# SCH_Project-SappY_2026-01-27.net
KiCad netlist of a schematic drawn in EasyEDA
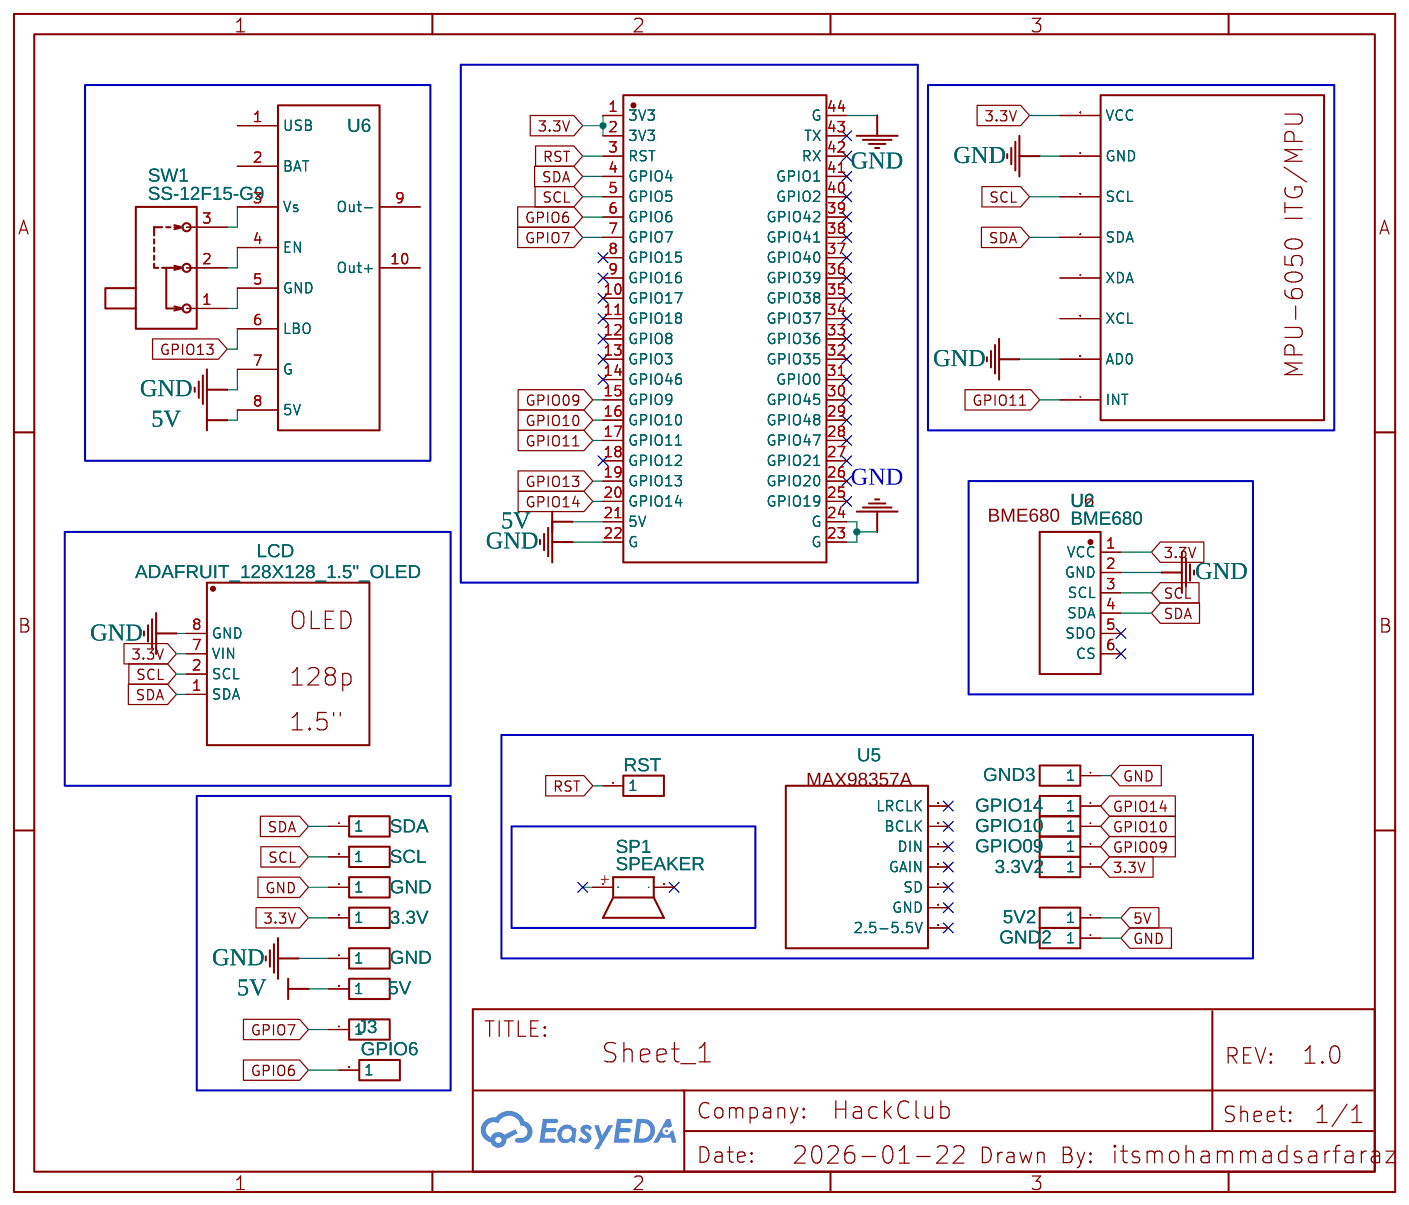
[diagram p0: schematic sheet]

(export (version "E")
  (design (tool "Eeschema 10.0.6"))
  (components
    (comp (ref "3.3V") (value "HDR-M-2.54_1x1") (libsource (lib "") (part "HDR-M-2.54_1x1_2")))
    (comp (ref "3.3V2") (value "HDR-M-2.54_1x1") (libsource (lib "") (part "HDR-M-2.54_1x1_8")))
    (comp (ref "5V2") (value "HDR-M-2.54_1x1") (libsource (lib "") (part "HDR-M-2.54_1x1_7")))
    (comp (ref "GND") (value "HDR-M-2.54_1x1") (libsource (lib "") (part "HDR-M-2.54_1x1_4")))
    (comp (ref "GND2") (value "HDR-M-2.54_1x1") (libsource (lib "") (part "HDR-M-2.54_1x1_5")))
    (comp (ref "GND3") (value "HDR-M-2.54_1x1") (libsource (lib "") (part "HDR-M-2.54_1x1_5")))
    (comp (ref "GPIO09") (value "HDR-M-2.54_1x1") (libsource (lib "") (part "HDR-M-2.54_1x1_1")))
    (comp (ref "GPIO10") (value "HDR-M-2.54_1x1") (libsource (lib "") (part "HDR-M-2.54_1x1_1")))
    (comp (ref "GPIO14") (value "HDR-M-2.54_1x1") (libsource (lib "") (part "HDR-M-2.54_1x1_1")))
    (comp (ref "J1") (value "GND") (libsource (lib "") (part "HDR-M-2.54_1x1")))
    (comp (ref "J2") (value "5V") (libsource (lib "") (part "HDR-M-2.54_1x1")))
    (comp (ref "J3") (value "HDR-M-2.54_1x1") (libsource (lib "") (part "HDR-M-2.54_1x1")))
    (comp (ref "J5") (value "GPIO6") (libsource (lib "") (part "HDR-M-2.54_1x1")))
    (comp (ref "LCD")
      (value "ADAFRUIT_128X128_1.5\"_OLED")
      (fields (field (name "Manufacturer Part") "MSP1503"))
      (libsource (lib "") (part "ADAFRUIT_128X128_1.5{dblquote}_OLED"))
    )
    (comp (ref "RST") (value "HDR-M-2.54_1x1") (libsource (lib "") (part "HDR-M-2.54_1x1_6")))
    (comp (ref "SCL") (value "HDR-M-2.54_1x1") (libsource (lib "") (part "HDR-M-2.54_1x1_9")))
    (comp (ref "SDA") (value "HDR-M-2.54_1x1") (libsource (lib "") (part "HDR-M-2.54_1x1_3")))
    (comp (ref "SP1") (value "SPEAKER") (libsource (lib "") (part "SPEAKER")))
    (comp (ref "SW1")
      (value "SS-12F15-G9")
      (fields (field (name "Manufacturer") "DEALON(德艺隆)"))
      (libsource (lib "") (part "SS-12F15-G9"))
    )
    (comp (ref "U1") (value "MPU-6050 ITG/MPU") (libsource (lib "") (part "MPU-6050 ITG/MPU")))
    (comp (ref "U2") (value "BME680") (libsource (lib "") (part "BME680")))
    (comp (ref "U4")
      (value "ESP32-S3-DevKitM-1U-N8")
      (fields
        (field (name "Manufacturer Part") "ESP32-S3-DevKitM-1")
        (field (name "Manufacturer") "Espressif")
      )
      (libsource (lib "") (part "ESP32-S3-DevKitM-1U-N8"))
    )
    (comp (ref "U5")
      (value "I2S MAX98357A MODULE")
      (fields (field (name "Manufacturer Part") "3006") (field (name "Manufacturer") "Adafruit"))
      (libsource (lib "") (part "I2S MAX98357A MODULE"))
    )
    (comp (ref "U6")
      (value "Adafruit Powerboost 1000C footprint")
      (fields (field (name "Manufacturer Part") "ada2465") (field (name "Manufacturer") "Adafruit"))
      (libsource (lib "") (part "Adafruit Powerboost 1000C footprint"))
    )
  )
  (nets
    (net (code "1") (name "3.3V") (class "Default")
      (node (ref "3.3V") (pin "1") (pinfunction "1_1") (pintype "input"))
      (node (ref "3.3V2") (pin "1") (pinfunction "1_1") (pintype "input"))
      (node (ref "LCD") (pin "7") (pinfunction "VIN_7") (pintype "unspecified"))
      (node (ref "U1") (pin "0") (pinfunction "VCC_0") (pintype "unspecified"))
      (node (ref "U2") (pin "1") (pinfunction "VCC_1") (pintype "unspecified"))
      (node (ref "U4") (pin "1") (pinfunction "3V3_1") (pintype "unspecified"))
      (node (ref "U4") (pin "2") (pinfunction "3V3_2") (pintype "unspecified"))
    )
    (net (code "2") (name "5V") (class "Default")
      (node (ref "5V2") (pin "1") (pinfunction "1_1") (pintype "input"))
      (node (ref "J2") (pin "1") (pinfunction "1_1") (pintype "input"))
      (node (ref "U4") (pin "21") (pinfunction "5V_21") (pintype "unspecified"))
      (node (ref "U6") (pin "8") (pinfunction "5V_8") (pintype "unspecified"))
    )
    (net (code "3") (name "GND") (class "Default")
      (node (ref "GND") (pin "1") (pinfunction "1_1") (pintype "input"))
      (node (ref "GND2") (pin "1") (pinfunction "1_1") (pintype "input"))
      (node (ref "GND3") (pin "1") (pinfunction "1_1") (pintype "input"))
      (node (ref "J1") (pin "1") (pinfunction "1_1") (pintype "input"))
      (node (ref "LCD") (pin "8") (pinfunction "GND_8") (pintype "unspecified"))
      (node (ref "U1") (pin "1") (pinfunction "GND_1") (pintype "unspecified"))
      (node (ref "U1") (pin "6") (pinfunction "AD0_6") (pintype "unspecified"))
      (node (ref "U2") (pin "2") (pinfunction "GND_2") (pintype "unspecified"))
      (node (ref "U4") (pin "22") (pinfunction "G_22") (pintype "unspecified"))
      (node (ref "U4") (pin "23") (pinfunction "G_23") (pintype "unspecified"))
      (node (ref "U4") (pin "24") (pinfunction "G_24") (pintype "unspecified"))
      (node (ref "U4") (pin "44") (pinfunction "G_44") (pintype "unspecified"))
      (node (ref "U6") (pin "7") (pinfunction "G_7") (pintype "unspecified"))
    )
    (net (code "4") (name "GPIO6") (class "Default")
      (node (ref "J3") (pin "1") (pinfunction "1_1") (pintype "input"))
      (node (ref "U4") (pin "6") (pinfunction "GPIO6_6") (pintype "unspecified"))
    )
    (net (code "5") (name "GPIO7") (class "Default")
      (node (ref "J5") (pin "1") (pinfunction "1_1") (pintype "input"))
      (node (ref "U4") (pin "7") (pinfunction "GPIO7_7") (pintype "unspecified"))
    )
    (net (code "6") (name "GPIO09") (class "Default")
      (node (ref "GPIO09") (pin "1") (pinfunction "1_1") (pintype "input"))
      (node (ref "U4") (pin "15") (pinfunction "GPIO9_15") (pintype "unspecified"))
    )
    (net (code "7") (name "GPIO10") (class "Default")
      (node (ref "GPIO10") (pin "1") (pinfunction "1_1") (pintype "input"))
      (node (ref "U4") (pin "16") (pinfunction "GPIO10_16") (pintype "unspecified"))
    )
    (net (code "8") (name "GPIO11") (class "Default")
      (node (ref "U1") (pin "7") (pinfunction "INT_7") (pintype "unspecified"))
      (node (ref "U4") (pin "17") (pinfunction "GPIO11_17") (pintype "unspecified"))
    )
    (net (code "9") (name "GPIO13") (class "Default")
      (node (ref "U4") (pin "19") (pinfunction "GPIO13_19") (pintype "unspecified"))
      (node (ref "U6") (pin "6") (pinfunction "LBO_6") (pintype "unspecified"))
    )
    (net (code "10") (name "GPIO14") (class "Default")
      (node (ref "GPIO14") (pin "1") (pinfunction "1_1") (pintype "input"))
      (node (ref "U4") (pin "20") (pinfunction "GPIO14_20") (pintype "unspecified"))
    )
    (net (code "11") (name "Net-(U6-EN)") (class "Default")
      (node (ref "SW1") (pin "2") (pinfunction "2_2") (pintype "unspecified"))
      (node (ref "U6") (pin "4") (pinfunction "EN_4") (pintype "unspecified"))
    )
    (net (code "12") (name "Net-(U6-GND)") (class "Default")
      (node (ref "SW1") (pin "1") (pinfunction "1_1") (pintype "unspecified"))
      (node (ref "U6") (pin "5") (pinfunction "GND_5") (pintype "unspecified"))
    )
    (net (code "13") (name "Net-(U6-Vs)") (class "Default")
      (node (ref "SW1") (pin "3") (pinfunction "3_3") (pintype "unspecified"))
      (node (ref "U6") (pin "3") (pinfunction "Vs_3") (pintype "unspecified"))
    )
    (net (code "14") (name "RST") (class "Default")
      (node (ref "RST") (pin "1") (pinfunction "1_1") (pintype "input"))
      (node (ref "U4") (pin "3") (pinfunction "RST_3") (pintype "unspecified"))
    )
    (net (code "15") (name "SCL") (class "Default")
      (node (ref "LCD") (pin "2") (pinfunction "SCL_2") (pintype "unspecified"))
      (node (ref "SCL") (pin "1") (pinfunction "1_1") (pintype "input"))
      (node (ref "U1") (pin "2") (pinfunction "SCL_2") (pintype "unspecified"))
      (node (ref "U2") (pin "3") (pinfunction "SCL_3") (pintype "unspecified"))
      (node (ref "U4") (pin "5") (pinfunction "GPIO5_5") (pintype "unspecified"))
    )
    (net (code "16") (name "SDA") (class "Default")
      (node (ref "LCD") (pin "1") (pinfunction "SDA_1") (pintype "unspecified"))
      (node (ref "SDA") (pin "1") (pinfunction "1_1") (pintype "input"))
      (node (ref "U1") (pin "3") (pinfunction "SDA_3") (pintype "unspecified"))
      (node (ref "U2") (pin "4") (pinfunction "SDA_4") (pintype "unspecified"))
      (node (ref "U4") (pin "4") (pinfunction "GPIO4_4") (pintype "unspecified"))
    )
    (net (code "17") (name "unconnected-(SP1-+-Pad1)") (class "Default")
      (node (ref "SP1") (pin "1") (pinfunction "+_1") (pintype "unspecified+no_connect"))
    )
    (net (code "18") (name "unconnected-(SP1---Pad2)") (class "Default")
      (node (ref "SP1") (pin "2") (pinfunction "-_2") (pintype "unspecified+no_connect"))
    )
    (net (code "19") (name "unconnected-(U1-XCL-Pad5)") (class "Default")
      (node (ref "U1") (pin "5") (pinfunction "XCL_5") (pintype "unspecified"))
    )
    (net (code "20") (name "unconnected-(U1-XDA-Pad4)") (class "Default")
      (node (ref "U1") (pin "4") (pinfunction "XDA_4") (pintype "unspecified"))
    )
    (net (code "21") (name "unconnected-(U2-CS-Pad6)") (class "Default")
      (node (ref "U2") (pin "6") (pinfunction "CS_6") (pintype "unspecified+no_connect"))
    )
    (net (code "22") (name "unconnected-(U2-SDO-Pad5)") (class "Default")
      (node (ref "U2") (pin "5") (pinfunction "SDO_5") (pintype "unspecified+no_connect"))
    )
    (net (code "23") (name "unconnected-(U4-GPIO0-Pad31)") (class "Default")
      (node (ref "U4") (pin "31") (pinfunction "GPIO0_31") (pintype "unspecified+no_connect"))
    )
    (net (code "24") (name "unconnected-(U4-GPIO1-Pad41)") (class "Default")
      (node (ref "U4") (pin "41") (pinfunction "GPIO1_41") (pintype "unspecified+no_connect"))
    )
    (net (code "25") (name "unconnected-(U4-GPIO2-Pad40)") (class "Default")
      (node (ref "U4") (pin "40") (pinfunction "GPIO2_40") (pintype "unspecified+no_connect"))
    )
    (net (code "26") (name "unconnected-(U4-GPIO3-Pad13)") (class "Default")
      (node (ref "U4") (pin "13") (pinfunction "GPIO3_13") (pintype "unspecified+no_connect"))
    )
    (net (code "27") (name "unconnected-(U4-GPIO8-Pad12)") (class "Default")
      (node (ref "U4") (pin "12") (pinfunction "GPIO8_12") (pintype "unspecified+no_connect"))
    )
    (net (code "28") (name "unconnected-(U4-GPIO12-Pad18)") (class "Default")
      (node (ref "U4") (pin "18") (pinfunction "GPIO12_18") (pintype "unspecified+no_connect"))
    )
    (net (code "29") (name "unconnected-(U4-GPIO15-Pad8)") (class "Default")
      (node (ref "U4") (pin "8") (pinfunction "GPIO15_8") (pintype "unspecified+no_connect"))
    )
    (net (code "30") (name "unconnected-(U4-GPIO16-Pad9)") (class "Default")
      (node (ref "U4") (pin "9") (pinfunction "GPIO16_9") (pintype "unspecified+no_connect"))
    )
    (net (code "31") (name "unconnected-(U4-GPIO17-Pad10)") (class "Default")
      (node (ref "U4") (pin "10") (pinfunction "GPIO17_10") (pintype "unspecified+no_connect"))
    )
    (net (code "32") (name "unconnected-(U4-GPIO18-Pad11)") (class "Default")
      (node (ref "U4") (pin "11") (pinfunction "GPIO18_11") (pintype "unspecified+no_connect"))
    )
    (net (code "33") (name "unconnected-(U4-GPIO19-Pad25)") (class "Default")
      (node (ref "U4") (pin "25") (pinfunction "GPIO19_25") (pintype "unspecified+no_connect"))
    )
    (net (code "34") (name "unconnected-(U4-GPIO20-Pad26)") (class "Default")
      (node (ref "U4") (pin "26") (pinfunction "GPIO20_26") (pintype "unspecified+no_connect"))
    )
    (net (code "35") (name "unconnected-(U4-GPIO21-Pad27)") (class "Default")
      (node (ref "U4") (pin "27") (pinfunction "GPIO21_27") (pintype "unspecified+no_connect"))
    )
    (net (code "36") (name "unconnected-(U4-GPIO35-Pad32)") (class "Default")
      (node (ref "U4") (pin "32") (pinfunction "GPIO35_32") (pintype "unspecified+no_connect"))
    )
    (net (code "37") (name "unconnected-(U4-GPIO36-Pad33)") (class "Default")
      (node (ref "U4") (pin "33") (pinfunction "GPIO36_33") (pintype "unspecified+no_connect"))
    )
    (net (code "38") (name "unconnected-(U4-GPIO37-Pad34)") (class "Default")
      (node (ref "U4") (pin "34") (pinfunction "GPIO37_34") (pintype "unspecified+no_connect"))
    )
    (net (code "39") (name "unconnected-(U4-GPIO38-Pad35)") (class "Default")
      (node (ref "U4") (pin "35") (pinfunction "GPIO38_35") (pintype "unspecified+no_connect"))
    )
    (net (code "40") (name "unconnected-(U4-GPIO39-Pad36)") (class "Default")
      (node (ref "U4") (pin "36") (pinfunction "GPIO39_36") (pintype "unspecified+no_connect"))
    )
    (net (code "41") (name "unconnected-(U4-GPIO40-Pad37)") (class "Default")
      (node (ref "U4") (pin "37") (pinfunction "GPIO40_37") (pintype "unspecified+no_connect"))
    )
    (net (code "42") (name "unconnected-(U4-GPIO41-Pad38)") (class "Default")
      (node (ref "U4") (pin "38") (pinfunction "GPIO41_38") (pintype "unspecified+no_connect"))
    )
    (net (code "43") (name "unconnected-(U4-GPIO42-Pad39)") (class "Default")
      (node (ref "U4") (pin "39") (pinfunction "GPIO42_39") (pintype "unspecified+no_connect"))
    )
    (net (code "44") (name "unconnected-(U4-GPIO45-Pad30)") (class "Default")
      (node (ref "U4") (pin "30") (pinfunction "GPIO45_30") (pintype "unspecified+no_connect"))
    )
    (net (code "45") (name "unconnected-(U4-GPIO46-Pad14)") (class "Default")
      (node (ref "U4") (pin "14") (pinfunction "GPIO46_14") (pintype "unspecified+no_connect"))
    )
    (net (code "46") (name "unconnected-(U4-GPIO47-Pad28)") (class "Default")
      (node (ref "U4") (pin "28") (pinfunction "GPIO47_28") (pintype "unspecified+no_connect"))
    )
    (net (code "47") (name "unconnected-(U4-GPIO48-Pad29)") (class "Default")
      (node (ref "U4") (pin "29") (pinfunction "GPIO48_29") (pintype "unspecified+no_connect"))
    )
    (net (code "48") (name "unconnected-(U4-RX-Pad42)") (class "Default")
      (node (ref "U4") (pin "42") (pinfunction "RX_42") (pintype "unspecified+no_connect"))
    )
    (net (code "49") (name "unconnected-(U4-TX-Pad43)") (class "Default")
      (node (ref "U4") (pin "43") (pinfunction "TX_43") (pintype "unspecified+no_connect"))
    )
    (net (code "50") (name "unconnected-(U5-2.5-5.5V-PadH7)") (class "Default")
      (node (ref "U5") (pin "H7") (pinfunction "2.5-5.5V_H7") (pintype "unspecified+no_connect"))
    )
    (net (code "51") (name "unconnected-(U5-BCLK-PadH2)") (class "Default")
      (node (ref "U5") (pin "H2") (pinfunction "BCLK_H2") (pintype "unspecified+no_connect"))
    )
    (net (code "52") (name "unconnected-(U5-DIN-PadH3)") (class "Default")
      (node (ref "U5") (pin "H3") (pinfunction "DIN_H3") (pintype "unspecified+no_connect"))
    )
    (net (code "53") (name "unconnected-(U5-GAIN-PadH4)") (class "Default")
      (node (ref "U5") (pin "H4") (pinfunction "GAIN_H4") (pintype "unspecified+no_connect"))
    )
    (net (code "54") (name "unconnected-(U5-GND-PadH6)") (class "Default")
      (node (ref "U5") (pin "H6") (pinfunction "GND_H6") (pintype "unspecified+no_connect"))
    )
    (net (code "55") (name "unconnected-(U5-LRCLK-PadH1)") (class "Default")
      (node (ref "U5") (pin "H1") (pinfunction "LRCLK_H1") (pintype "unspecified+no_connect"))
    )
    (net (code "56") (name "unconnected-(U5-SD-PadH5)") (class "Default")
      (node (ref "U5") (pin "H5") (pinfunction "SD_H5") (pintype "unspecified+no_connect"))
    )
    (net (code "57") (name "unconnected-(U6-BAT-Pad2)") (class "Default")
      (node (ref "U6") (pin "2") (pinfunction "BAT_2") (pintype "unspecified"))
    )
    (net (code "58") (name "unconnected-(U6-Out+-Pad10)") (class "Default")
      (node (ref "U6") (pin "10") (pinfunction "Out+_10") (pintype "unspecified"))
    )
    (net (code "59") (name "unconnected-(U6-Out--Pad9)") (class "Default")
      (node (ref "U6") (pin "9") (pinfunction "Out-_9") (pintype "unspecified"))
    )
    (net (code "60") (name "unconnected-(U6-USB-Pad1)") (class "Default")
      (node (ref "U6") (pin "1") (pinfunction "USB_1") (pintype "unspecified"))
    )
  )
)
